# P04_POWER.net
KiCad netlist of a schematic drawn in Altium Designer
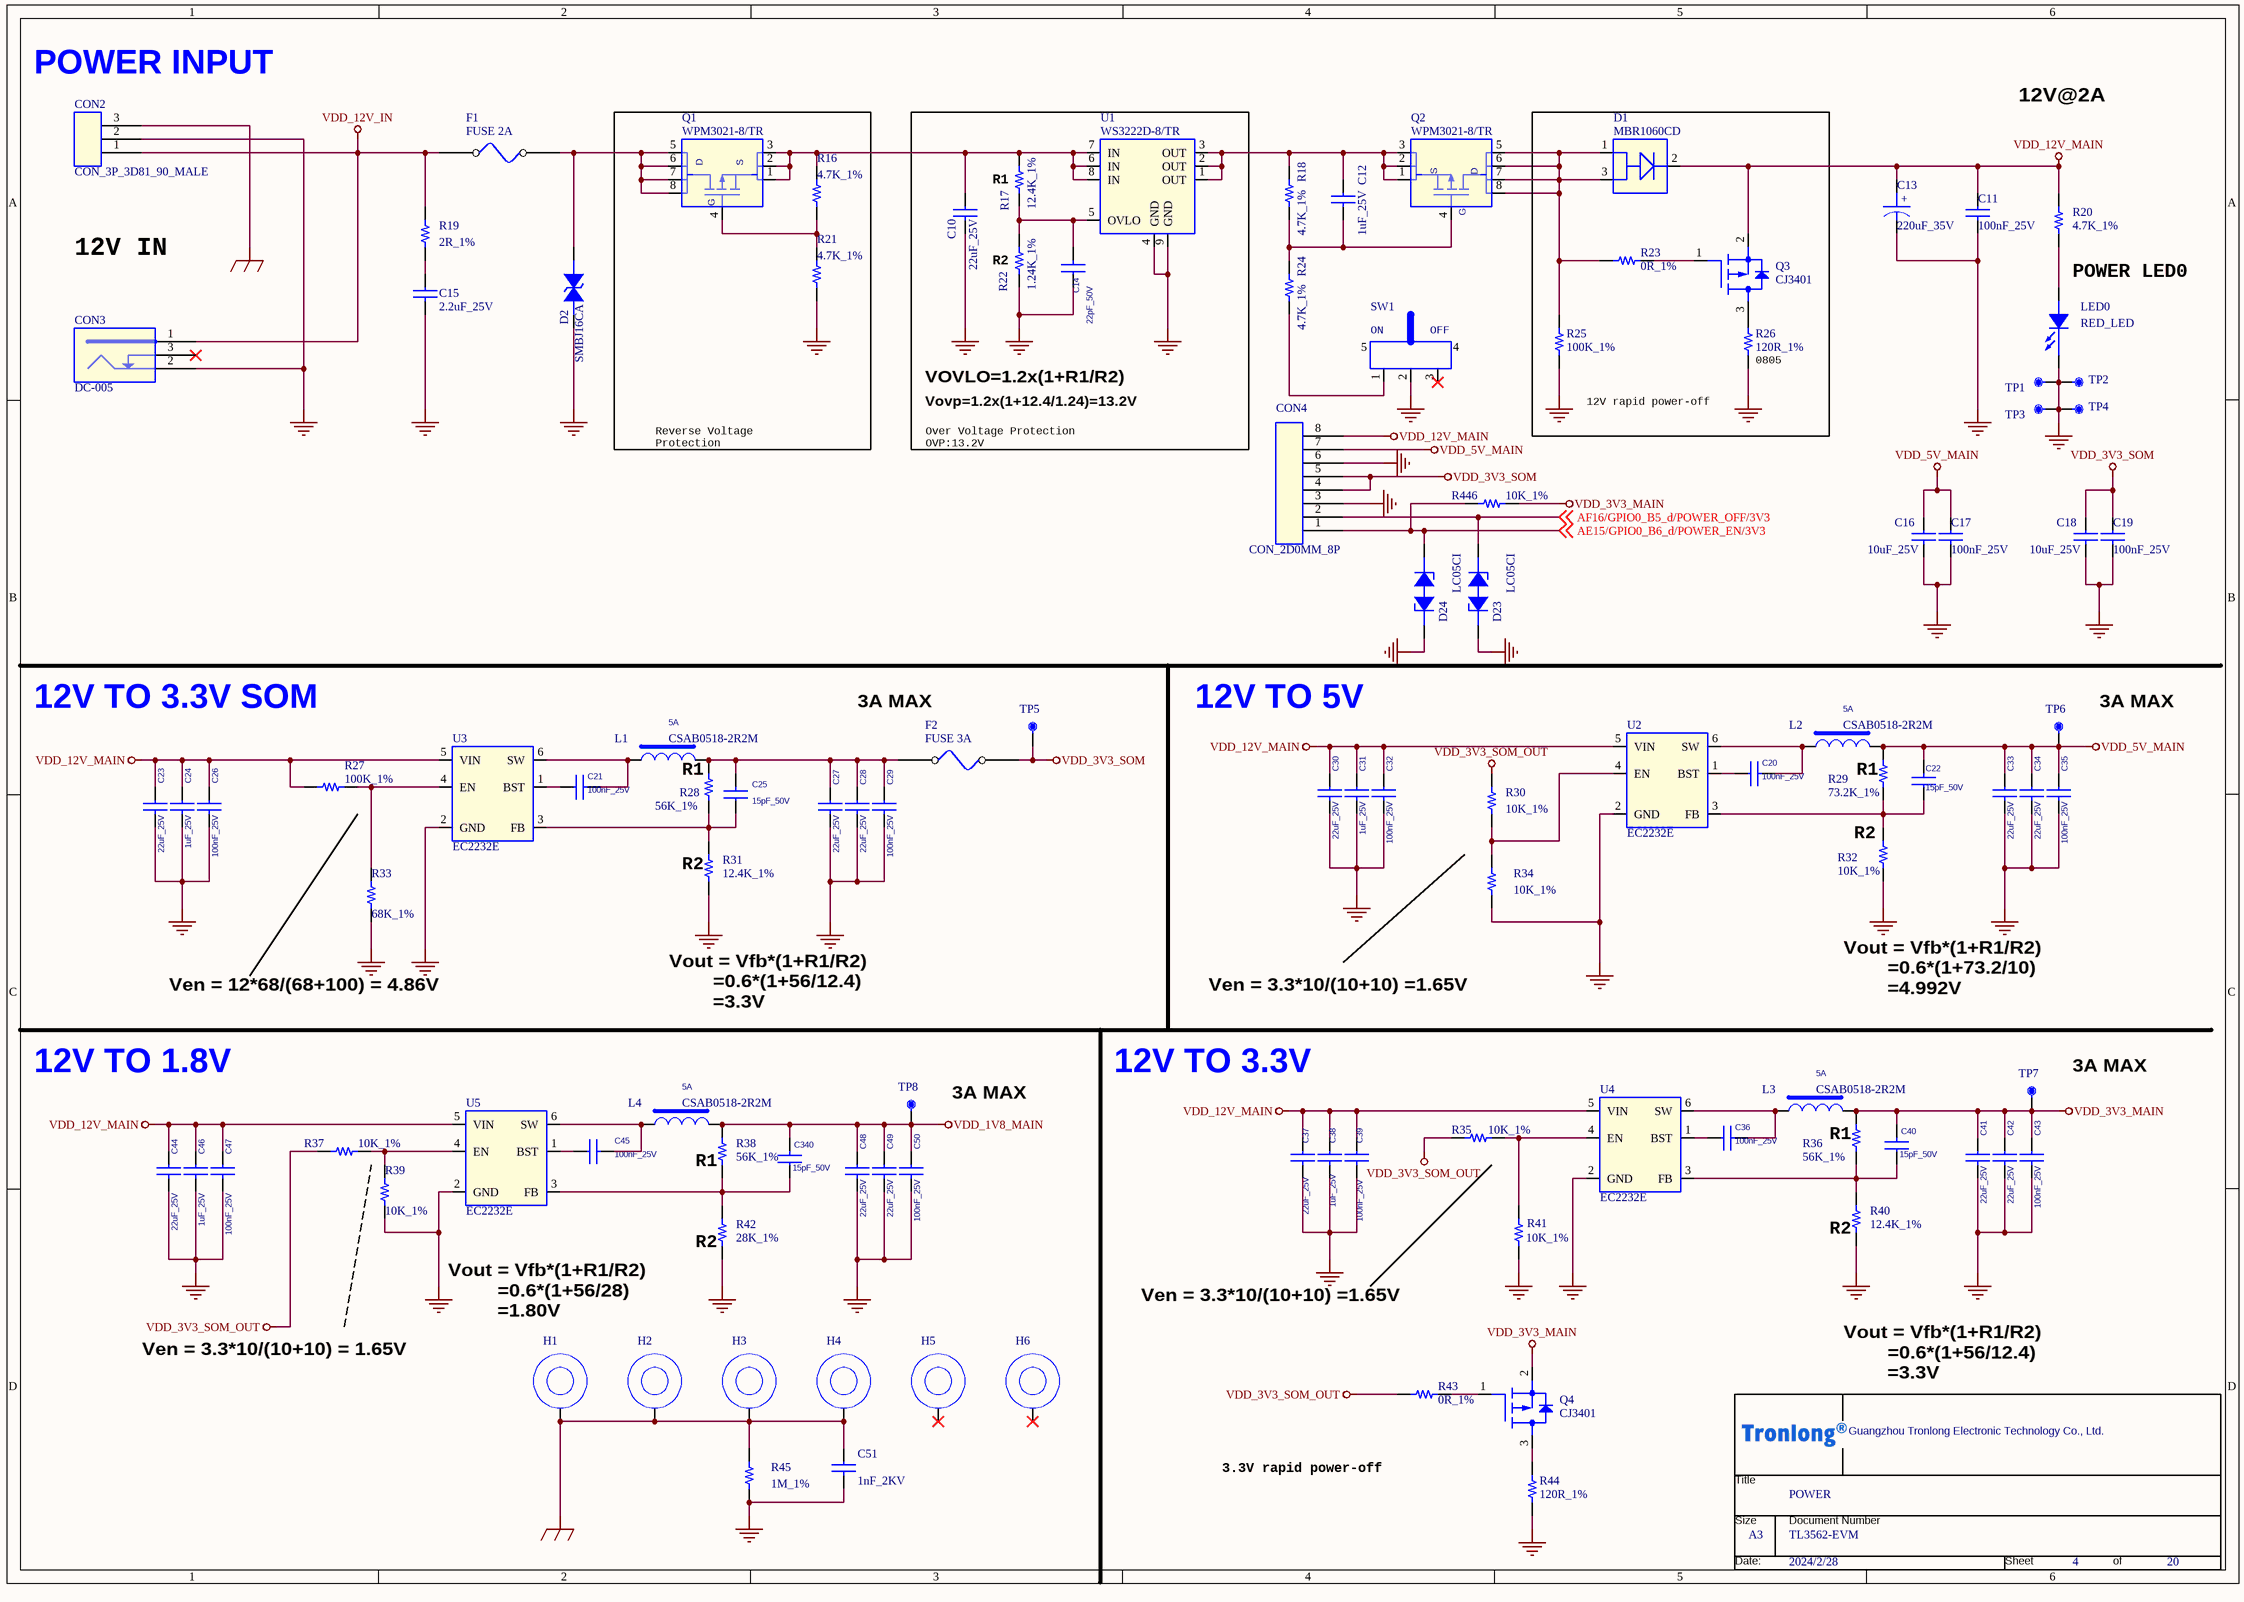
[diagram p0: P04_POWER.SchDoc]

(export (version "E")
  (design (tool "Eeschema 10.0.6"))
  (components
    (comp (ref "C10")
      (value "22uF_25V")
      (footprint "C0805")
      (description "贴片陶瓷电容,22uF,20%,25V,X5R")
      (libsource (lib "*") (part "CAP NP_Dup3"))
    )
    (comp (ref "C11")
      (value "100nF_25V")
      (footprint "C0402")
      (description "贴片陶瓷电容,100nF,10%,25V,X5R")
      (libsource (lib "*") (part "CAP NP_Dup3"))
    )
    (comp (ref "C12")
      (value "1uF_25V")
      (footprint "C0603")
      (description "贴片陶瓷电容,1uF,10%,25V,X5R")
      (libsource (lib "*") (part "CAP NP_Dup3"))
    )
    (comp (ref "C13")
      (value "220uF_35V")
      (footprint "cap_alu_smd_8x10d5")
      (description "贴片式铝电解电容,220uF,20%,35V")
      (fields
        (field (name "MANUFACTURER PARTNUMBER") "RVT1V221M0810VG")
        (field (name "MANUFACTURER") "东莞市合粤电子有限公司（Heyue）")
      )
      (libsource (lib "*") (part "CAP POL_Dup1"))
    )
    (comp (ref "C14")
      (value "22pF_50V")
      (footprint "C0603")
      (description "贴片陶瓷电容,22pF,5%,50V,C0G")
      (libsource (lib "*") (part "CAP NP_Dup3"))
    )
    (comp (ref "C15")
      (value "2.2uF_25V")
      (footprint "C1206")
      (description "贴片陶瓷电容,2.2uF,20%,25V,Y5V")
      (libsource (lib "*") (part "CAP NP_Dup3"))
    )
    (comp (ref "C16")
      (value "10uF_25V")
      (footprint "C0603")
      (description "贴片陶瓷电容,10uF,10%,10V,X5R")
      (libsource (lib "*") (part "CAP NP_Dup3"))
    )
    (comp (ref "C17")
      (value "100nF_25V")
      (footprint "C0402")
      (description "贴片陶瓷电容,100nF,10%,25V,X5R")
      (libsource (lib "*") (part "CAP NP_Dup3"))
    )
    (comp (ref "C18")
      (value "10uF_25V")
      (footprint "C0603")
      (description "贴片陶瓷电容,10uF,10%,10V,X5R")
      (libsource (lib "*") (part "CAP NP_Dup3"))
    )
    (comp (ref "C19")
      (value "100nF_25V")
      (footprint "C0402")
      (description "贴片陶瓷电容,100nF,10%,25V,X5R")
      (libsource (lib "*") (part "CAP NP_Dup3"))
    )
    (comp (ref "C20")
      (value "100nF_25V")
      (footprint "C0402")
      (description "贴片陶瓷电容,100nF,10%,25V,X5R")
      (libsource (lib "*") (part "CAP NP_Dup3"))
    )
    (comp (ref "C21")
      (value "100nF_25V")
      (footprint "C0402")
      (description "贴片陶瓷电容,100nF,10%,25V,X5R")
      (libsource (lib "*") (part "CAP NP_Dup3"))
    )
    (comp (ref "C22")
      (value "15pF_50V")
      (footprint "C0402")
      (description "贴片陶瓷电容,15pF,5%,50V,COG")
      (libsource (lib "*") (part "CAP NP_Dup3"))
    )
    (comp (ref "C23")
      (value "22uF_25V")
      (footprint "C0805")
      (description "贴片陶瓷电容,22uF,20%,25V,X5R")
      (libsource (lib "*") (part "CAP NP_Dup3"))
    )
    (comp (ref "C24")
      (value "1uF_25V")
      (footprint "C0603")
      (description "贴片陶瓷电容,1uF,10%,25V,X5R")
      (libsource (lib "*") (part "CAP NP_Dup3"))
    )
    (comp (ref "C25")
      (value "15pF_50V")
      (footprint "C0402")
      (description "贴片陶瓷电容,15pF,5%,50V,COG")
      (libsource (lib "*") (part "CAP NP_Dup3"))
    )
    (comp (ref "C26")
      (value "100nF_25V")
      (footprint "C0402")
      (description "贴片陶瓷电容,100nF,10%,25V,X5R")
      (libsource (lib "*") (part "CAP NP_Dup3"))
    )
    (comp (ref "C27")
      (value "22uF_25V")
      (footprint "C0805")
      (description "贴片陶瓷电容,22uF,20%,25V,X5R")
      (libsource (lib "*") (part "CAP NP_Dup3"))
    )
    (comp (ref "C28")
      (value "22uF_25V")
      (footprint "C0805")
      (description "贴片陶瓷电容,22uF,20%,25V,X5R")
      (libsource (lib "*") (part "CAP NP_Dup3"))
    )
    (comp (ref "C29")
      (value "100nF_25V")
      (footprint "C0402")
      (description "贴片陶瓷电容,100nF,10%,25V,X5R")
      (libsource (lib "*") (part "CAP NP_Dup3"))
    )
    (comp (ref "C30")
      (value "22uF_25V")
      (footprint "C0805")
      (description "贴片陶瓷电容,22uF,20%,25V,X5R")
      (libsource (lib "*") (part "CAP NP_Dup3"))
    )
    (comp (ref "C31")
      (value "1uF_25V")
      (footprint "C0603")
      (description "贴片陶瓷电容,1uF,10%,25V,X5R")
      (libsource (lib "*") (part "CAP NP_Dup3"))
    )
    (comp (ref "C32")
      (value "100nF_25V")
      (footprint "C0402")
      (description "贴片陶瓷电容,100nF,10%,25V,X5R")
      (libsource (lib "*") (part "CAP NP_Dup3"))
    )
    (comp (ref "C33")
      (value "22uF_25V")
      (footprint "C0805")
      (description "贴片陶瓷电容,22uF,20%,25V,X5R")
      (libsource (lib "*") (part "CAP NP_Dup3"))
    )
    (comp (ref "C34")
      (value "22uF_25V")
      (footprint "C0805")
      (description "贴片陶瓷电容,22uF,20%,25V,X5R")
      (libsource (lib "*") (part "CAP NP_Dup3"))
    )
    (comp (ref "C35")
      (value "100nF_25V")
      (footprint "C0402")
      (description "贴片陶瓷电容,100nF,10%,25V,X5R")
      (libsource (lib "*") (part "CAP NP_Dup3"))
    )
    (comp (ref "C36")
      (value "100nF_25V")
      (footprint "C0402")
      (description "贴片陶瓷电容,100nF,10%,25V,X5R")
      (libsource (lib "*") (part "CAP NP_Dup3"))
    )
    (comp (ref "C37")
      (value "22uF_25V")
      (footprint "C0805")
      (description "贴片陶瓷电容,22uF,20%,25V,X5R")
      (libsource (lib "*") (part "CAP NP_Dup3"))
    )
    (comp (ref "C38")
      (value "1uF_25V")
      (footprint "C0603")
      (description "贴片陶瓷电容,1uF,10%,25V,X5R")
      (libsource (lib "*") (part "CAP NP_Dup3"))
    )
    (comp (ref "C39")
      (value "100nF_25V")
      (footprint "C0402")
      (description "贴片陶瓷电容,100nF,10%,25V,X5R")
      (libsource (lib "*") (part "CAP NP_Dup3"))
    )
    (comp (ref "C40")
      (value "15pF_50V")
      (footprint "C0402")
      (description "贴片陶瓷电容,15pF,5%,50V,COG")
      (libsource (lib "*") (part "CAP NP_Dup3"))
    )
    (comp (ref "C41")
      (value "22uF_25V")
      (footprint "C0805")
      (description "贴片陶瓷电容,22uF,20%,25V,X5R")
      (libsource (lib "*") (part "CAP NP_Dup3"))
    )
    (comp (ref "C42")
      (value "22uF_25V")
      (footprint "C0805")
      (description "贴片陶瓷电容,22uF,20%,25V,X5R")
      (libsource (lib "*") (part "CAP NP_Dup3"))
    )
    (comp (ref "C43")
      (value "100nF_25V")
      (footprint "C0402")
      (description "贴片陶瓷电容,100nF,10%,25V,X5R")
      (libsource (lib "*") (part "CAP NP_Dup3"))
    )
    (comp (ref "C44")
      (value "22uF_25V")
      (footprint "C0805")
      (description "贴片陶瓷电容,22uF,20%,25V,X5R")
      (libsource (lib "*") (part "CAP NP_Dup3"))
    )
    (comp (ref "C45")
      (value "100nF_25V")
      (footprint "C0402")
      (description "贴片陶瓷电容,100nF,10%,25V,X5R")
      (libsource (lib "*") (part "CAP NP_Dup3"))
    )
    (comp (ref "C46")
      (value "1uF_25V")
      (footprint "C0603")
      (description "贴片陶瓷电容,1uF,10%,25V,X5R")
      (libsource (lib "*") (part "CAP NP_Dup3"))
    )
    (comp (ref "C47")
      (value "100nF_25V")
      (footprint "C0402")
      (description "贴片陶瓷电容,100nF,10%,25V,X5R")
      (libsource (lib "*") (part "CAP NP_Dup3"))
    )
    (comp (ref "C48")
      (value "22uF_25V")
      (footprint "C0805")
      (description "贴片陶瓷电容,22uF,20%,25V,X5R")
      (libsource (lib "*") (part "CAP NP_Dup3"))
    )
    (comp (ref "C49")
      (value "22uF_25V")
      (footprint "C0805")
      (description "贴片陶瓷电容,22uF,20%,25V,X5R")
      (libsource (lib "*") (part "CAP NP_Dup3"))
    )
    (comp (ref "C50")
      (value "100nF_25V")
      (footprint "C0402")
      (description "贴片陶瓷电容,100nF,10%,25V,X5R")
      (libsource (lib "*") (part "CAP NP_Dup3"))
    )
    (comp (ref "C51")
      (value "1nF_2KV")
      (footprint "C1210")
      (description "贴片陶瓷电容,1nF,10%,2KV,X7R")
      (libsource (lib "*") (part "CAP NP_Dup3"))
    )
    (comp (ref "C340")
      (value "15pF_50V")
      (footprint "C0402")
      (description "贴片陶瓷电容,15pF,5%,50V,COG")
      (libsource (lib "*") (part "CAP NP_Dup3"))
    )
    (comp (ref "CON2")
      (value "CON_3P_3D81_90_MALE")
      (footprint "CON_3P_3D81_90_MALE_NEW")
      (description "端子座,3PIN,间距3.81MM,90度,绿色,插件")
      (fields
        (field (name "MANUFACTURER PARTNUMBER") "KF2EDGR-3.81-03P-14")
        (field (name "MANUFACTURER") "慈溪市科发电子有限公司（KEFA）")
      )
      (libsource (lib "*") (part "CON3_Dup1"))
    )
    (comp (ref "CON3")
      (value "DC-005")
      (footprint "con_dc005_new")
      (description "DC-005,3PIN,90度,母座,2.0MM内径,插件")
      (fields
        (field (name "MANUFACTURER") "广东纳特康电子股份有限公司(natconn)")
        (field (name "MANUFACTURER PARTNUMBER") "305-OT03SZD001")
      )
      (libsource (lib "*") (part "DC-005"))
    )
    (comp (ref "CON4")
      (value "CON_2D0MM_8P")
      (footprint "DIP_CON_2D0MM_8P")
      (description "端子座,1x8PIN,间距2.00MM,180度,插件")
      (fields
        (field (name "MANUFACTURER") "深圳市长江连接器有限公司（CJT）")
        (field (name "MANUFACTURER PARTNUMBER") "A2001WV-8P-3")
      )
      (libsource (lib "*") (part "CON8"))
    )
    (comp (ref "D1")
      (value "MBR1060CD")
      (footprint "TO-252")
      (description "肖特基二极管,VR=60V,IF=10A,VF=0.75V@5A,两路")
      (fields (field (name "MANUFACTURER") "辽宁芯诺电子科技有限公司（XINNUO）"))
      (libsource (lib "*") (part "MBRB1045_0"))
    )
    (comp (ref "D2")
      (value "SMBJ16CA")
      (footprint "SMB")
      (description "TVS二极管,VRWM=16V,VBR=17.8V,一组,双向")
      (fields (field (name "MANUFACTURER") "江苏长晶科技有限公司（JSCJ）"))
      (libsource (lib "*") (part "DIODE-TRIG"))
    )
    (comp (ref "D23")
      (value "LC05CI")
      (footprint "SOD323_BI")
      (description "TVS二极管,VRWM=5V,VBR=6V,一组,双向,30KV,30KV")
      (fields
        (field (name "MANUFACTURER PART NUMBER") "PESD3V3L1BA")
        (field (name "MANUFACTURER") "上海雷卯电子科技有限公司（Leiditech）")
      )
      (libsource (lib "*") (part "DIODE BREAKDOWN_2"))
    )
    (comp (ref "D24")
      (value "LC05CI")
      (footprint "SOD323_BI")
      (description "TVS二极管,VRWM=5V,VBR=6V,一组,双向,30KV,30KV")
      (fields
        (field (name "MANUFACTURER PART NUMBER") "PESD3V3L1BA")
        (field (name "MANUFACTURER") "上海雷卯电子科技有限公司（Leiditech）")
      )
      (libsource (lib "*") (part "DIODE BREAKDOWN_2"))
    )
    (comp (ref "F1")
      (value "FUSE 2A")
      (footprint "F1206")
      (description "保险丝，Vmax=72V,Imax=50A,Ihold=2A")
      (fields
        (field (name "MANUFACTURER PARTNUMBER") "F12T2")
        (field (name "MANUFACTURER") "东莞市竞沃电子科技有限公司（TLC）")
      )
      (libsource (lib "*") (part "FUSE"))
    )
    (comp (ref "F2")
      (value "FUSE 3A")
      (footprint "F1206")
      (description "保险丝，Vmax=72V,Imax=50A,Ihold=3A")
      (fields
        (field (name "MANUFACTURER PARTNUMBER") "F12T3")
        (field (name "MANUFACTURER") "东莞市竞沃电子科技有限公司（TLC）")
      )
      (libsource (lib "*") (part "FUSE"))
    )
    (comp (ref "H1") (value "HOLE") (footprint "MHOLE_C200D125") (libsource (lib "*") (part "HOLE")))
    (comp (ref "H2") (value "HOLE") (footprint "MHOLE_C200D125") (libsource (lib "*") (part "HOLE")))
    (comp (ref "H3") (value "HOLE") (footprint "MHOLE_C200D125") (libsource (lib "*") (part "HOLE")))
    (comp (ref "H4") (value "HOLE") (footprint "MHOLE_C200D125") (libsource (lib "*") (part "HOLE")))
    (comp (ref "H5") (value "HOLE") (footprint "MHOLE_C200D125") (libsource (lib "*") (part "HOLE")))
    (comp (ref "H6") (value "HOLE") (footprint "MHOLE_C200D125") (libsource (lib "*") (part "HOLE")))
    (comp (ref "L1")
      (value "CSAB0518-2R2M")
      (footprint "SMD_CSAB0518")
      (description "贴片功率电感,2.2uH,0.035Ω,Isat=6.5A,Irms=5A")
      (fields (field (name "MANUFACTURER") "深圳市科达嘉电子有限公司（CODACA）") (field (name "CURRENT") "5A"))
      (libsource (lib "TL3562-EVM-A1-0-000-D-20231116") (part "INDUCTOR"))
    )
    (comp (ref "L2")
      (value "CSAB0518-2R2M")
      (footprint "SMD_CSAB0518")
      (description "贴片功率电感,2.2uH,0.035Ω,Isat=6.5A,Irms=5A")
      (fields (field (name "MANUFACTURER") "深圳市科达嘉电子有限公司（CODACA）") (field (name "CURRENT") "5A"))
      (libsource (lib "TL3562-EVM-A1-0-000-D-20231116") (part "INDUCTOR"))
    )
    (comp (ref "L3")
      (value "CSAB0518-2R2M")
      (footprint "SMD_CSAB0518")
      (description "贴片功率电感,2.2uH,0.035Ω,Isat=6.5A,Irms=5A")
      (fields (field (name "MANUFACTURER") "深圳市科达嘉电子有限公司（CODACA）") (field (name "CURRENT") "5A"))
      (libsource (lib "TL3562-EVM-A1-0-000-D-20231116") (part "INDUCTOR"))
    )
    (comp (ref "L4")
      (value "CSAB0518-2R2M")
      (footprint "SMD_CSAB0518")
      (description "贴片功率电感,2.2uH,0.035Ω,Isat=6.5A,Irms=5A")
      (fields (field (name "MANUFACTURER") "深圳市科达嘉电子有限公司（CODACA）") (field (name "CURRENT") "5A"))
      (libsource (lib "TL3562-EVM-A1-0-000-D-20231116") (part "INDUCTOR"))
    )
    (comp (ref "LED0")
      (value "RED_LED")
      (footprint "CON_2P_3MM")
      (description "直插式发光二极管,红色,带灯座")
      (fields
        (field (name "MANUFACTURER PARTNUMBER") "JH-03B2RD1E-DL")
        (field (name "MANUFACTURER") "深圳市巨弘光电有限公司（JUHLIGHT）")
      )
      (libsource (lib "*") (part "LED"))
    )
    (comp (ref "Q1")
      (value "WPM3021-8/TR")
      (footprint "PSOPSOP-8L")
      (description "MOSFET,P沟道,VDSS=-30V,VGSS=±25V,ID=-13A,PD=3.8W,VGS(th)=-3V")
      (fields (field (name "MANUFACTURER") "上海韦尔半导体股份有限公司（WILLSEMI）"))
      (libsource (lib "*") (part "WPM3021"))
    )
    (comp (ref "Q2")
      (value "WPM3021-8/TR")
      (footprint "PSOPSOP-8L")
      (description "MOSFET,P沟道,VDSS=-30V,VGSS=±25V,ID=-13A,PD=3.8W,VGS(th)=-3V")
      (fields (field (name "MANUFACTURER") "上海韦尔半导体股份有限公司（WILLSEMI）"))
      (libsource (lib "") (part "WPM3021_1"))
    )
    (comp (ref "Q3")
      (value "CJ3401")
      (footprint "SOT23-3")
      (description "MOSFET,P沟道,VDSS=-30V,VGSS=±12V,ID=-4.2A,PD=0.35W,VGS(th)=-1.3V")
      (fields (field (name "MANUFACTURER") "江苏长晶科技有限公司（JSCJ）"))
      (libsource (lib "*") (part "MOSFET P SOT_Dup1"))
    )
    (comp (ref "Q4")
      (value "CJ3401")
      (footprint "SOT23-3")
      (description "MOSFET,P沟道,VDSS=-30V,VGSS=±12V,ID=-4.2A,PD=0.35W,VGS(th)=-1.3V")
      (fields (field (name "MANUFACTURER") "江苏长晶科技有限公司（JSCJ）"))
      (libsource (lib "*") (part "MOSFET P SOT_Dup1"))
    )
    (comp (ref "R16")
      (value "4.7K_1%")
      (footprint "R0402")
      (description "贴片电阻,4.7K,±1%,1/16W")
      (libsource (lib "*") (part "Resistor_Dup3"))
    )
    (comp (ref "R17")
      (value "12.4K_1%")
      (footprint "R0402")
      (description "贴片电阻,12.4K,±1%,1/16W")
      (libsource (lib "*") (part "Resistor_Dup3"))
    )
    (comp (ref "R18")
      (value "4.7K_1%")
      (footprint "R0402")
      (description "贴片电阻,4.7K,±1%,1/16W")
      (libsource (lib "*") (part "Resistor_Dup3"))
    )
    (comp (ref "R19")
      (value "2R_1%")
      (footprint "R1210")
      (description "贴片电阻,2R,±1%,1/3W")
      (libsource (lib "*") (part "Resistor_Dup3"))
    )
    (comp (ref "R20")
      (value "4.7K_1%")
      (footprint "R0402")
      (description "贴片电阻,4.7K,±1%,1/16W")
      (libsource (lib "*") (part "Resistor_Dup3"))
    )
    (comp (ref "R21")
      (value "4.7K_1%")
      (footprint "R0402")
      (description "贴片电阻,4.7K,±1%,1/16W")
      (libsource (lib "*") (part "Resistor_Dup3"))
    )
    (comp (ref "R22")
      (value "1.24K_1%")
      (footprint "R0603")
      (description "贴片电阻,12.4K,±1%,1/10W")
      (libsource (lib "*") (part "Resistor_Dup3"))
    )
    (comp (ref "R23")
      (value "0R_1%")
      (footprint "R0402")
      (description "0R,±1%,R0402,≥1/16W")
      (libsource (lib "*") (part "Resistor_Dup3"))
    )
    (comp (ref "R24")
      (value "4.7K_1%")
      (footprint "R0402")
      (description "贴片电阻,4.7K,±1%,1/16W")
      (libsource (lib "*") (part "Resistor_Dup3"))
    )
    (comp (ref "R25")
      (value "100K_1%")
      (footprint "R0402")
      (description "贴片电阻,100K,±1%,1/16W")
      (libsource (lib "*") (part "Resistor_Dup3"))
    )
    (comp (ref "R26")
      (value "120R_1%")
      (footprint "R0805")
      (description "贴片电阻,120R,±1%,1/8W")
      (libsource (lib "*") (part "Resistor_Dup3"))
    )
    (comp (ref "R27")
      (value "100K_1%")
      (footprint "R0402")
      (description "贴片电阻,100K,±1%,1/16W")
      (libsource (lib "*") (part "Resistor_Dup3"))
    )
    (comp (ref "R28")
      (value "56K_1%")
      (footprint "R0402")
      (description "贴片电阻,56K,±1%,1/16W")
      (libsource (lib "*") (part "Resistor_Dup3"))
    )
    (comp (ref "R29")
      (value "73.2K_1%")
      (footprint "R0402")
      (description "贴片电阻,73.2K,±1%,1/16W")
      (libsource (lib "*") (part "Resistor_Dup3"))
    )
    (comp (ref "R30")
      (value "10K_1%")
      (footprint "R0402")
      (description "贴片电阻,10K,±1%,1/16W")
      (libsource (lib "*") (part "Resistor_Dup3"))
    )
    (comp (ref "R31")
      (value "12.4K_1%")
      (footprint "R0402")
      (description "贴片电阻,12.4K,±1%,1/16W")
      (libsource (lib "*") (part "Resistor_Dup3"))
    )
    (comp (ref "R32")
      (value "10K_1%")
      (footprint "R0402")
      (description "贴片电阻,10K,±1%,1/16W")
      (libsource (lib "*") (part "Resistor_Dup3"))
    )
    (comp (ref "R33")
      (value "68K_1%")
      (footprint "R0402")
      (description "贴片电阻,68K,±1%,1/16W")
      (libsource (lib "*") (part "Resistor_Dup3"))
    )
    (comp (ref "R34")
      (value "10K_1%")
      (footprint "R0402")
      (description "贴片电阻,10K,±1%,1/16W")
      (libsource (lib "*") (part "Resistor_Dup3"))
    )
    (comp (ref "R35")
      (value "10K_1%")
      (footprint "R0402")
      (description "贴片电阻,10K,±1%,1/16W")
      (libsource (lib "*") (part "Resistor_Dup3"))
    )
    (comp (ref "R36")
      (value "56K_1%")
      (footprint "R0402")
      (description "贴片电阻,56K,±1%,1/16W")
      (libsource (lib "*") (part "Resistor_Dup3"))
    )
    (comp (ref "R37")
      (value "10K_1%")
      (footprint "R0402")
      (description "贴片电阻,10K,±1%,1/16W")
      (libsource (lib "*") (part "Resistor_Dup3"))
    )
    (comp (ref "R38")
      (value "56K_1%")
      (footprint "R0402")
      (description "贴片电阻,56K,±1%,1/16W")
      (libsource (lib "*") (part "Resistor_Dup3"))
    )
    (comp (ref "R39")
      (value "10K_1%")
      (footprint "R0402")
      (description "贴片电阻,10K,±1%,1/16W")
      (libsource (lib "*") (part "Resistor_Dup3"))
    )
    (comp (ref "R40")
      (value "12.4K_1%")
      (footprint "R0402")
      (description "贴片电阻,12.4K,±1%,1/16W")
      (libsource (lib "*") (part "Resistor_Dup3"))
    )
    (comp (ref "R41")
      (value "10K_1%")
      (footprint "R0402")
      (description "贴片电阻,10K,±1%,1/16W")
      (libsource (lib "*") (part "Resistor_Dup3"))
    )
    (comp (ref "R42")
      (value "28K_1%")
      (footprint "R0402")
      (description "28K,±1%,R0402,≥1/16W")
      (libsource (lib "*") (part "Resistor_Dup3"))
    )
    (comp (ref "R43")
      (value "0R_1%")
      (footprint "R0402")
      (description "0R,±1%,R0402,≥1/16W")
      (libsource (lib "*") (part "Resistor_Dup3"))
    )
    (comp (ref "R44")
      (value "120R_1%")
      (footprint "R0805")
      (description "贴片电阻,120R,±1%,1/8W")
      (libsource (lib "*") (part "Resistor_Dup3"))
    )
    (comp (ref "R45")
      (value "1M_1%")
      (footprint "R0603")
      (description "贴片电阻,1M,±1%,1/10W")
      (libsource (lib "*") (part "Resistor_Dup3"))
    )
    (comp (ref "R446")
      (value "10K_1%")
      (footprint "R0402")
      (description "贴片电阻,10K,±1%,1/16W")
      (libsource (lib "*") (part "Resistor_Dup3"))
    )
    (comp (ref "SW1")
      (value "SS-12D11L5")
      (footprint "sw-126_76")
      (description "拨动开关，2档3脚侧拨开关,黑色,90度,短柄")
      (fields (field (name "MANUFACTURER") "广东星坤科技股份有限公司（XKB）"))
      (libsource (lib "*") (part "switch_7"))
    )
    (comp (ref "TP1")
      (value "Black Test Point")
      (footprint "TP_DIP")
      (description "黑色直插测试柱")
      (fields
        (field (name "MANUFACTURER") "深圳市保定五金塑胶有限公司")
        (field (name "MANUFACTURER PARTNUMBER") "TP-5011")
      )
      (libsource (lib "*") (part "TP-S40"))
    )
    (comp (ref "TP2")
      (value "Black Test Point")
      (footprint "TP_DIP")
      (description "黑色直插测试柱")
      (fields
        (field (name "MANUFACTURER PARTNUMBER") "TP-5011")
        (field (name "MANUFACTURER") "深圳市保定五金塑胶有限公司")
      )
      (libsource (lib "*") (part "TP-S40"))
    )
    (comp (ref "TP3")
      (value "Black Test Point")
      (footprint "TP_DIP")
      (description "黑色直插测试柱")
      (fields
        (field (name "MANUFACTURER") "深圳市保定五金塑胶有限公司")
        (field (name "MANUFACTURER PARTNUMBER") "TP-5011")
      )
      (libsource (lib "*") (part "TP-S40"))
    )
    (comp (ref "TP4")
      (value "Black Test Point")
      (footprint "TP_DIP")
      (description "黑色直插测试柱")
      (fields
        (field (name "MANUFACTURER") "深圳市保定五金塑胶有限公司")
        (field (name "MANUFACTURER PARTNUMBER") "TP-5011")
      )
      (libsource (lib "*") (part "TP-S40"))
    )
    (comp (ref "TP5") (value "SMT TP") (footprint "TP30") (libsource (lib "*") (part "TP-S40")))
    (comp (ref "TP6") (value "SMT TP") (footprint "TP30") (libsource (lib "*") (part "TP-S40")))
    (comp (ref "TP7") (value "SMT TP") (footprint "TP30") (libsource (lib "*") (part "TP-S40")))
    (comp (ref "TP8") (value "SMT TP") (footprint "TP30") (libsource (lib "*") (part "TP-S40")))
    (comp (ref "U1")
      (value "WS3222D-8/TR")
      (footprint "DFN2X2-8L")
      (description "MOSFET,P沟道,VDSS=-30V,VGSS=±25V,ID=-13A,PD=3.8W,VGS(th)=-3V")
      (fields (field (name "MANUFACTURER") "上海韦尔半导体股份有限公司（WILLSEMI）"))
      (libsource (lib "*") (part "WS3222D-8/TR"))
    )
    (comp (ref "U2")
      (value "EC2232E")
      (footprint "SOT-23-6L")
      (description "DC/DC,Buck,Vin:4.5V~17V,Vout:0.6V~6V,3A,1路")
      (fields (field (name "MANUFACTURER") "上海芯强微电子股份有限公司（Ecranic）"))
      (libsource (lib "*") (part "WD1304E30"))
    )
    (comp (ref "U3")
      (value "EC2232E")
      (footprint "SOT-23-6L")
      (description "DC/DC,Buck,Vin:4.5V~17V,Vout:0.6V~6V,3A,1路")
      (fields (field (name "MANUFACTURER") "上海芯强微电子股份有限公司（Ecranic）"))
      (libsource (lib "*") (part "WD1304E30"))
    )
    (comp (ref "U4")
      (value "EC2232E")
      (footprint "SOT-23-6L")
      (description "DC/DC,Buck,Vin:4.5V~17V,Vout:0.6V~6V,3A,1路")
      (fields (field (name "MANUFACTURER") "上海芯强微电子股份有限公司（Ecranic）"))
      (libsource (lib "*") (part "WD1304E30"))
    )
    (comp (ref "U5")
      (value "EC2232E")
      (footprint "SOT-23-6L")
      (description "DC/DC,Buck,Vin:4.5V~17V,Vout:0.6V~6V,3A,1路")
      (fields (field (name "MANUFACTURER") "上海芯强微电子股份有限公司（Ecranic）"))
      (libsource (lib "*") (part "WD1304E30_0"))
    )
  )
  (nets
    (net (code "1") (name "AE15{slash}GPIO0_B6_d{slash}POWER_EN{slash}3V3") (class "Default")
      (node (ref "CON4") (pin "1") (pinfunction "1_1") (pintype "passive"))
      (node (ref "D24") (pin "1") (pinfunction "ANODE1_1") (pintype "passive"))
      (node (ref "R446") (pin "2") (pinfunction "2_2") (pintype "passive"))
    )
    (net (code "2") (name "AF16{slash}GPIO0_B5_d{slash}POWER_OFF{slash}3V3") (class "Default")
      (node (ref "CON4") (pin "2") (pinfunction "2_2") (pintype "passive"))
      (node (ref "D23") (pin "1") (pinfunction "ANODE1_1") (pintype "passive"))
    )
    (net (code "3") (name "EGND") (class "Default")
      (node (ref "C51") (pin "1") (pinfunction "1_1") (pintype "passive"))
      (node (ref "CON2") (pin "3") (pinfunction "3_3") (pintype "passive"))
      (node (ref "H1") (pin "1") (pinfunction "1_1") (pintype "passive"))
      (node (ref "H2") (pin "1") (pinfunction "1_1") (pintype "passive"))
      (node (ref "H3") (pin "1") (pinfunction "1_1") (pintype "passive"))
      (node (ref "H4") (pin "1") (pinfunction "1_1") (pintype "passive"))
      (node (ref "R45") (pin "1") (pinfunction "1_1") (pintype "passive"))
    )
    (net (code "4") (name "GND") (class "Default")
      (node (ref "C10") (pin "2") (pinfunction "2_2") (pintype "passive"))
      (node (ref "C11") (pin "2") (pinfunction "2_2") (pintype "passive"))
      (node (ref "C13") (pin "2") (pinfunction "2_2") (pintype "passive"))
      (node (ref "C14") (pin "1") (pinfunction "1_1") (pintype "passive"))
      (node (ref "C15") (pin "2") (pinfunction "2_2") (pintype "passive"))
      (node (ref "C16") (pin "2") (pinfunction "2_2") (pintype "passive"))
      (node (ref "C17") (pin "2") (pinfunction "2_2") (pintype "passive"))
      (node (ref "C18") (pin "2") (pinfunction "2_2") (pintype "passive"))
      (node (ref "C19") (pin "2") (pinfunction "2_2") (pintype "passive"))
      (node (ref "C23") (pin "2") (pinfunction "2_2") (pintype "passive"))
      (node (ref "C24") (pin "2") (pinfunction "2_2") (pintype "passive"))
      (node (ref "C26") (pin "2") (pinfunction "2_2") (pintype "passive"))
      (node (ref "C27") (pin "2") (pinfunction "2_2") (pintype "passive"))
      (node (ref "C28") (pin "2") (pinfunction "2_2") (pintype "passive"))
      (node (ref "C29") (pin "2") (pinfunction "2_2") (pintype "passive"))
      (node (ref "C30") (pin "2") (pinfunction "2_2") (pintype "passive"))
      (node (ref "C31") (pin "2") (pinfunction "2_2") (pintype "passive"))
      (node (ref "C32") (pin "2") (pinfunction "2_2") (pintype "passive"))
      (node (ref "C33") (pin "2") (pinfunction "2_2") (pintype "passive"))
      (node (ref "C34") (pin "2") (pinfunction "2_2") (pintype "passive"))
      (node (ref "C35") (pin "2") (pinfunction "2_2") (pintype "passive"))
      (node (ref "C37") (pin "2") (pinfunction "2_2") (pintype "passive"))
      (node (ref "C38") (pin "2") (pinfunction "2_2") (pintype "passive"))
      (node (ref "C39") (pin "2") (pinfunction "2_2") (pintype "passive"))
      (node (ref "C41") (pin "2") (pinfunction "2_2") (pintype "passive"))
      (node (ref "C42") (pin "2") (pinfunction "2_2") (pintype "passive"))
      (node (ref "C43") (pin "2") (pinfunction "2_2") (pintype "passive"))
      (node (ref "C44") (pin "2") (pinfunction "2_2") (pintype "passive"))
      (node (ref "C46") (pin "2") (pinfunction "2_2") (pintype "passive"))
      (node (ref "C47") (pin "2") (pinfunction "2_2") (pintype "passive"))
      (node (ref "C48") (pin "2") (pinfunction "2_2") (pintype "passive"))
      (node (ref "C49") (pin "2") (pinfunction "2_2") (pintype "passive"))
      (node (ref "C50") (pin "2") (pinfunction "2_2") (pintype "passive"))
      (node (ref "C51") (pin "2") (pinfunction "2_2") (pintype "passive"))
      (node (ref "CON2") (pin "2") (pinfunction "2_2") (pintype "passive"))
      (node (ref "CON3") (pin "2") (pinfunction "22_2") (pintype "passive"))
      (node (ref "CON4") (pin "3") (pinfunction "3_3") (pintype "passive"))
      (node (ref "CON4") (pin "6") (pinfunction "6_6") (pintype "passive"))
      (node (ref "D2") (pin "1") (pinfunction "1_1") (pintype "passive"))
      (node (ref "D23") (pin "2") (pinfunction "CATHODE2_2") (pintype "passive"))
      (node (ref "D24") (pin "2") (pinfunction "CATHODE2_2") (pintype "passive"))
      (node (ref "LED0") (pin "2") (pinfunction "CATHODE_2") (pintype "passive"))
      (node (ref "R21") (pin "1") (pinfunction "1_1") (pintype "passive"))
      (node (ref "R22") (pin "2") (pinfunction "2_2") (pintype "passive"))
      (node (ref "R25") (pin "1") (pinfunction "1_1") (pintype "passive"))
      (node (ref "R26") (pin "2") (pinfunction "2_2") (pintype "passive"))
      (node (ref "R31") (pin "1") (pinfunction "1_1") (pintype "passive"))
      (node (ref "R32") (pin "1") (pinfunction "1_1") (pintype "passive"))
      (node (ref "R33") (pin "1") (pinfunction "1_1") (pintype "passive"))
      (node (ref "R34") (pin "1") (pinfunction "1_1") (pintype "passive"))
      (node (ref "R39") (pin "1") (pinfunction "1_1") (pintype "passive"))
      (node (ref "R40") (pin "1") (pinfunction "1_1") (pintype "passive"))
      (node (ref "R41") (pin "1") (pinfunction "1_1") (pintype "passive"))
      (node (ref "R42") (pin "1") (pinfunction "1_1") (pintype "passive"))
      (node (ref "R44") (pin "2") (pinfunction "2_2") (pintype "passive"))
      (node (ref "R45") (pin "2") (pinfunction "2_2") (pintype "passive"))
      (node (ref "SW1") (pin "2") (pinfunction "2_2") (pintype "passive"))
      (node (ref "TP1") (pin "1") (pinfunction "1_1") (pintype "passive"))
      (node (ref "TP2") (pin "1") (pinfunction "1_1") (pintype "passive"))
      (node (ref "TP3") (pin "1") (pinfunction "1_1") (pintype "passive"))
      (node (ref "TP4") (pin "1") (pinfunction "1_1") (pintype "passive"))
      (node (ref "U1") (pin "4") (pinfunction "GND_4") (pintype "power_in"))
      (node (ref "U1") (pin "9") (pinfunction "GND_9") (pintype "power_in"))
      (node (ref "U2") (pin "2") (pinfunction "GND_2") (pintype "power_in"))
      (node (ref "U3") (pin "2") (pinfunction "GND_2") (pintype "power_in"))
      (node (ref "U4") (pin "2") (pinfunction "GND_2") (pintype "power_in"))
      (node (ref "U5") (pin "2") (pinfunction "GND_2") (pintype "power_in"))
    )
    (net (code "5") (name "Net-(C15-Pad1)") (class "Default")
      (node (ref "C15") (pin "1") (pinfunction "1_1") (pintype "passive"))
      (node (ref "R19") (pin "1") (pinfunction "1_1") (pintype "passive"))
    )
    (net (code "6") (name "Net-(C25-Pad2)") (class "Default")
      (node (ref "C25") (pin "2") (pinfunction "2_2") (pintype "passive"))
      (node (ref "C27") (pin "1") (pinfunction "1_1") (pintype "passive"))
      (node (ref "C28") (pin "1") (pinfunction "1_1") (pintype "passive"))
      (node (ref "C29") (pin "1") (pinfunction "1_1") (pintype "passive"))
      (node (ref "F2") (pin "1") (pinfunction "1_1") (pintype "passive"))
      (node (ref "L1") (pin "2") (pinfunction "2_2") (pintype "passive"))
      (node (ref "R28") (pin "2") (pinfunction "2_2") (pintype "passive"))
    )
    (net (code "7") (name "Net-(LED0-ANODE)") (class "Default")
      (node (ref "LED0") (pin "1") (pinfunction "ANODE_1") (pintype "passive"))
      (node (ref "R20") (pin "2") (pinfunction "2_2") (pintype "passive"))
    )
    (net (code "8") (name "Net-(Q1-D1)") (class "Default")
      (node (ref "D2") (pin "2") (pinfunction "2_2") (pintype "passive"))
      (node (ref "F1") (pin "2") (pinfunction "2_2") (pintype "passive"))
      (node (ref "Q1") (pin "5") (pinfunction "D1_5") (pintype "passive"))
      (node (ref "Q1") (pin "6") (pinfunction "D2_6") (pintype "passive"))
      (node (ref "Q1") (pin "7") (pinfunction "D3_7") (pintype "passive"))
      (node (ref "Q1") (pin "8") (pinfunction "D4_8") (pintype "passive"))
    )
    (net (code "9") (name "Net-(Q1-G)") (class "Default")
      (node (ref "Q1") (pin "4") (pinfunction "G_4") (pintype "passive"))
      (node (ref "R16") (pin "1") (pinfunction "1_1") (pintype "passive"))
      (node (ref "R21") (pin "2") (pinfunction "2_2") (pintype "passive"))
    )
    (net (code "10") (name "Net-(Q1-S1)") (class "Default")
      (node (ref "C10") (pin "1") (pinfunction "1_1") (pintype "passive"))
      (node (ref "Q1") (pin "1") (pinfunction "S1_1") (pintype "passive"))
      (node (ref "Q1") (pin "2") (pinfunction "S2_2") (pintype "passive"))
      (node (ref "Q1") (pin "3") (pinfunction "S3_3") (pintype "passive"))
      (node (ref "R16") (pin "2") (pinfunction "2_2") (pintype "passive"))
      (node (ref "R17") (pin "1") (pinfunction "1_1") (pintype "passive"))
      (node (ref "U1") (pin "6") (pinfunction "IN_6") (pintype "power_in"))
      (node (ref "U1") (pin "7") (pinfunction "IN_7") (pintype "power_in"))
      (node (ref "U1") (pin "8") (pinfunction "IN_8") (pintype "power_in"))
    )
    (net (code "11") (name "Net-(Q2-D1)") (class "Default")
      (node (ref "D1") (pin "1") (pinfunction "1_1") (pintype "passive"))
      (node (ref "D1") (pin "3") (pinfunction "3_3") (pintype "passive"))
      (node (ref "Q2") (pin "5") (pinfunction "D1_5") (pintype "passive"))
      (node (ref "Q2") (pin "6") (pinfunction "D2_6") (pintype "passive"))
      (node (ref "Q2") (pin "7") (pinfunction "D3_7") (pintype "passive"))
      (node (ref "Q2") (pin "8") (pinfunction "D4_8") (pintype "passive"))
      (node (ref "R23") (pin "2") (pinfunction "2_2") (pintype "passive"))
      (node (ref "R25") (pin "2") (pinfunction "2_2") (pintype "passive"))
    )
    (net (code "12") (name "Net-(Q2-G)") (class "Default")
      (node (ref "C12") (pin "2") (pinfunction "2_2") (pintype "passive"))
      (node (ref "Q2") (pin "4") (pinfunction "G_4") (pintype "passive"))
      (node (ref "R18") (pin "1") (pinfunction "1_1") (pintype "passive"))
      (node (ref "R24") (pin "2") (pinfunction "2_2") (pintype "passive"))
    )
    (net (code "13") (name "Net-(Q2-S1)") (class "Default")
      (node (ref "C12") (pin "1") (pinfunction "1_1") (pintype "passive"))
      (node (ref "Q2") (pin "1") (pinfunction "S1_1") (pintype "passive"))
      (node (ref "Q2") (pin "2") (pinfunction "S2_2") (pintype "passive"))
      (node (ref "Q2") (pin "3") (pinfunction "S3_3") (pintype "passive"))
      (node (ref "R18") (pin "2") (pinfunction "2_2") (pintype "passive"))
      (node (ref "U1") (pin "1") (pinfunction "OUT_1") (pintype "power_in"))
      (node (ref "U1") (pin "2") (pinfunction "OUT_2") (pintype "power_in"))
      (node (ref "U1") (pin "3") (pinfunction "OUT_3") (pintype "power_in"))
    )
    (net (code "14") (name "Net-(Q3-DRAIN)") (class "Default")
      (node (ref "Q3") (pin "3") (pinfunction "DRAIN_3") (pintype "passive"))
      (node (ref "R26") (pin "1") (pinfunction "1_1") (pintype "passive"))
    )
    (net (code "15") (name "Net-(Q3-GATE)") (class "Default")
      (node (ref "Q3") (pin "1") (pinfunction "GATE_1") (pintype "passive"))
      (node (ref "R23") (pin "1") (pinfunction "1_1") (pintype "passive"))
    )
    (net (code "16") (name "Net-(Q4-DRAIN)") (class "Default")
      (node (ref "Q4") (pin "3") (pinfunction "DRAIN_3") (pintype "passive"))
      (node (ref "R44") (pin "1") (pinfunction "1_1") (pintype "passive"))
    )
    (net (code "17") (name "Net-(Q4-GATE)") (class "Default")
      (node (ref "Q4") (pin "1") (pinfunction "GATE_1") (pintype "passive"))
      (node (ref "R43") (pin "1") (pinfunction "1_1") (pintype "passive"))
    )
    (net (code "18") (name "Net-(R24-Pad1)") (class "Default")
      (node (ref "R24") (pin "1") (pinfunction "1_1") (pintype "passive"))
      (node (ref "SW1") (pin "1") (pinfunction "1_1") (pintype "passive"))
    )
    (net (code "19") (name "Net-(U1-OVLO)") (class "Default")
      (node (ref "C14") (pin "2") (pinfunction "2_2") (pintype "passive"))
      (node (ref "R17") (pin "2") (pinfunction "2_2") (pintype "passive"))
      (node (ref "R22") (pin "1") (pinfunction "1_1") (pintype "passive"))
      (node (ref "U1") (pin "5") (pinfunction "OVLO_5") (pintype "passive"))
    )
    (net (code "20") (name "Net-(U2-BST)") (class "Default")
      (node (ref "C20") (pin "1") (pinfunction "1_1") (pintype "passive"))
      (node (ref "U2") (pin "1") (pinfunction "BST_1") (pintype "passive"))
    )
    (net (code "21") (name "Net-(U2-EN)") (class "Default")
      (node (ref "R30") (pin "1") (pinfunction "1_1") (pintype "passive"))
      (node (ref "R34") (pin "2") (pinfunction "2_2") (pintype "passive"))
      (node (ref "U2") (pin "4") (pinfunction "EN_4") (pintype "passive"))
    )
    (net (code "22") (name "Net-(U2-FB)") (class "Default")
      (node (ref "C22") (pin "1") (pinfunction "1_1") (pintype "passive"))
      (node (ref "R29") (pin "1") (pinfunction "1_1") (pintype "passive"))
      (node (ref "R32") (pin "2") (pinfunction "2_2") (pintype "passive"))
      (node (ref "U2") (pin "3") (pinfunction "FB_3") (pintype "passive"))
    )
    (net (code "23") (name "Net-(U2-SW)") (class "Default")
      (node (ref "C20") (pin "2") (pinfunction "2_2") (pintype "passive"))
      (node (ref "L2") (pin "1") (pinfunction "1_1") (pintype "passive"))
      (node (ref "U2") (pin "6") (pinfunction "SW_6") (pintype "passive"))
    )
    (net (code "24") (name "Net-(U3-BST)") (class "Default")
      (node (ref "C21") (pin "1") (pinfunction "1_1") (pintype "passive"))
      (node (ref "U3") (pin "1") (pinfunction "BST_1") (pintype "passive"))
    )
    (net (code "25") (name "Net-(U3-EN)") (class "Default")
      (node (ref "R27") (pin "2") (pinfunction "2_2") (pintype "passive"))
      (node (ref "R33") (pin "2") (pinfunction "2_2") (pintype "passive"))
      (node (ref "U3") (pin "4") (pinfunction "EN_4") (pintype "passive"))
    )
    (net (code "26") (name "Net-(U3-FB)") (class "Default")
      (node (ref "C25") (pin "1") (pinfunction "1_1") (pintype "passive"))
      (node (ref "R28") (pin "1") (pinfunction "1_1") (pintype "passive"))
      (node (ref "R31") (pin "2") (pinfunction "2_2") (pintype "passive"))
      (node (ref "U3") (pin "3") (pinfunction "FB_3") (pintype "passive"))
    )
    (net (code "27") (name "Net-(U3-SW)") (class "Default")
      (node (ref "C21") (pin "2") (pinfunction "2_2") (pintype "passive"))
      (node (ref "L1") (pin "1") (pinfunction "1_1") (pintype "passive"))
      (node (ref "U3") (pin "6") (pinfunction "SW_6") (pintype "passive"))
    )
    (net (code "28") (name "Net-(U4-BST)") (class "Default")
      (node (ref "C36") (pin "1") (pinfunction "1_1") (pintype "passive"))
      (node (ref "U4") (pin "1") (pinfunction "BST_1") (pintype "passive"))
    )
    (net (code "29") (name "Net-(U4-EN)") (class "Default")
      (node (ref "R35") (pin "1") (pinfunction "1_1") (pintype "passive"))
      (node (ref "R41") (pin "2") (pinfunction "2_2") (pintype "passive"))
      (node (ref "U4") (pin "4") (pinfunction "EN_4") (pintype "passive"))
    )
    (net (code "30") (name "Net-(U4-FB)") (class "Default")
      (node (ref "C40") (pin "1") (pinfunction "1_1") (pintype "passive"))
      (node (ref "R36") (pin "1") (pinfunction "1_1") (pintype "passive"))
      (node (ref "R40") (pin "2") (pinfunction "2_2") (pintype "passive"))
      (node (ref "U4") (pin "3") (pinfunction "FB_3") (pintype "passive"))
    )
    (net (code "31") (name "Net-(U4-SW)") (class "Default")
      (node (ref "C36") (pin "2") (pinfunction "2_2") (pintype "passive"))
      (node (ref "L3") (pin "1") (pinfunction "1_1") (pintype "passive"))
      (node (ref "U4") (pin "6") (pinfunction "SW_6") (pintype "passive"))
    )
    (net (code "32") (name "Net-(U5-BST)") (class "Default")
      (node (ref "C45") (pin "1") (pinfunction "1_1") (pintype "passive"))
      (node (ref "U5") (pin "1") (pinfunction "BST_1") (pintype "passive"))
    )
    (net (code "33") (name "Net-(U5-EN)") (class "Default")
      (node (ref "R37") (pin "2") (pinfunction "2_2") (pintype "passive"))
      (node (ref "R39") (pin "2") (pinfunction "2_2") (pintype "passive"))
      (node (ref "U5") (pin "4") (pinfunction "EN_4") (pintype "passive"))
    )
    (net (code "34") (name "Net-(U5-FB)") (class "Default")
      (node (ref "C340") (pin "1") (pinfunction "1_1") (pintype "passive"))
      (node (ref "R38") (pin "1") (pinfunction "1_1") (pintype "passive"))
      (node (ref "R42") (pin "2") (pinfunction "2_2") (pintype "passive"))
      (node (ref "U5") (pin "3") (pinfunction "FB_3") (pintype "passive"))
    )
    (net (code "35") (name "Net-(U5-SW)") (class "Default")
      (node (ref "C45") (pin "2") (pinfunction "2_2") (pintype "passive"))
      (node (ref "L4") (pin "1") (pinfunction "1_1") (pintype "passive"))
      (node (ref "U5") (pin "6") (pinfunction "SW_6") (pintype "passive"))
    )
    (net (code "36") (name "VDD_1V8_MAIN") (class "Default")
      (node (ref "C340") (pin "2") (pinfunction "2_2") (pintype "passive"))
      (node (ref "C48") (pin "1") (pinfunction "1_1") (pintype "passive"))
      (node (ref "C49") (pin "1") (pinfunction "1_1") (pintype "passive"))
      (node (ref "C50") (pin "1") (pinfunction "1_1") (pintype "passive"))
      (node (ref "L4") (pin "2") (pinfunction "2_2") (pintype "passive"))
      (node (ref "R38") (pin "2") (pinfunction "2_2") (pintype "passive"))
      (node (ref "TP8") (pin "1") (pinfunction "1_1") (pintype "passive"))
    )
    (net (code "37") (name "VDD_3V3_MAIN") (class "Default")
      (node (ref "C40") (pin "2") (pinfunction "2_2") (pintype "passive"))
      (node (ref "C41") (pin "1") (pinfunction "1_1") (pintype "passive"))
      (node (ref "C42") (pin "1") (pinfunction "1_1") (pintype "passive"))
      (node (ref "C43") (pin "1") (pinfunction "1_1") (pintype "passive"))
      (node (ref "L3") (pin "2") (pinfunction "2_2") (pintype "passive"))
      (node (ref "Q4") (pin "2") (pinfunction "SOURCE_2") (pintype "passive"))
      (node (ref "R36") (pin "2") (pinfunction "2_2") (pintype "passive"))
      (node (ref "R446") (pin "1") (pinfunction "1_1") (pintype "passive"))
      (node (ref "TP7") (pin "1") (pinfunction "1_1") (pintype "passive"))
    )
    (net (code "38") (name "VDD_3V3_SOM") (class "Default")
      (node (ref "C18") (pin "1") (pinfunction "1_1") (pintype "passive"))
      (node (ref "C19") (pin "1") (pinfunction "1_1") (pintype "passive"))
      (node (ref "CON4") (pin "4") (pinfunction "4_4") (pintype "passive"))
      (node (ref "CON4") (pin "5") (pinfunction "5_5") (pintype "passive"))
      (node (ref "F2") (pin "2") (pinfunction "2_2") (pintype "passive"))
      (node (ref "TP5") (pin "1") (pinfunction "1_1") (pintype "passive"))
    )
    (net (code "39") (name "VDD_3V3_SOM_OUT") (class "Default")
      (node (ref "R30") (pin "2") (pinfunction "2_2") (pintype "passive"))
      (node (ref "R35") (pin "2") (pinfunction "2_2") (pintype "passive"))
      (node (ref "R37") (pin "1") (pinfunction "1_1") (pintype "passive"))
      (node (ref "R43") (pin "2") (pinfunction "2_2") (pintype "passive"))
    )
    (net (code "40") (name "VDD_5V_MAIN") (class "Default")
      (node (ref "C16") (pin "1") (pinfunction "1_1") (pintype "passive"))
      (node (ref "C17") (pin "1") (pinfunction "1_1") (pintype "passive"))
      (node (ref "C22") (pin "2") (pinfunction "2_2") (pintype "passive"))
      (node (ref "C33") (pin "1") (pinfunction "1_1") (pintype "passive"))
      (node (ref "C34") (pin "1") (pinfunction "1_1") (pintype "passive"))
      (node (ref "C35") (pin "1") (pinfunction "1_1") (pintype "passive"))
      (node (ref "CON4") (pin "7") (pinfunction "7_7") (pintype "passive"))
      (node (ref "L2") (pin "2") (pinfunction "2_2") (pintype "passive"))
      (node (ref "R29") (pin "2") (pinfunction "2_2") (pintype "passive"))
      (node (ref "TP6") (pin "1") (pinfunction "1_1") (pintype "passive"))
    )
    (net (code "41") (name "VDD_12V_IN") (class "Default")
      (node (ref "CON2") (pin "1") (pinfunction "1_1") (pintype "passive"))
      (node (ref "CON3") (pin "1") (pinfunction "1_1") (pintype "passive"))
      (node (ref "F1") (pin "1") (pinfunction "1_1") (pintype "passive"))
      (node (ref "R19") (pin "2") (pinfunction "2_2") (pintype "passive"))
    )
    (net (code "42") (name "VDD_12V_MAIN") (class "Default")
      (node (ref "C11") (pin "1") (pinfunction "1_1") (pintype "passive"))
      (node (ref "C13") (pin "1") (pinfunction "1_1") (pintype "passive"))
      (node (ref "C23") (pin "1") (pinfunction "1_1") (pintype "passive"))
      (node (ref "C24") (pin "1") (pinfunction "1_1") (pintype "passive"))
      (node (ref "C26") (pin "1") (pinfunction "1_1") (pintype "passive"))
      (node (ref "C30") (pin "1") (pinfunction "1_1") (pintype "passive"))
      (node (ref "C31") (pin "1") (pinfunction "1_1") (pintype "passive"))
      (node (ref "C32") (pin "1") (pinfunction "1_1") (pintype "passive"))
      (node (ref "C37") (pin "1") (pinfunction "1_1") (pintype "passive"))
      (node (ref "C38") (pin "1") (pinfunction "1_1") (pintype "passive"))
      (node (ref "C39") (pin "1") (pinfunction "1_1") (pintype "passive"))
      (node (ref "C44") (pin "1") (pinfunction "1_1") (pintype "passive"))
      (node (ref "C46") (pin "1") (pinfunction "1_1") (pintype "passive"))
      (node (ref "C47") (pin "1") (pinfunction "1_1") (pintype "passive"))
      (node (ref "CON4") (pin "8") (pinfunction "8_8") (pintype "passive"))
      (node (ref "D1") (pin "2") (pinfunction "2_2") (pintype "passive"))
      (node (ref "Q3") (pin "2") (pinfunction "SOURCE_2") (pintype "passive"))
      (node (ref "R20") (pin "1") (pinfunction "1_1") (pintype "passive"))
      (node (ref "R27") (pin "1") (pinfunction "1_1") (pintype "passive"))
      (node (ref "U2") (pin "5") (pinfunction "VIN_5") (pintype "power_in"))
      (node (ref "U3") (pin "5") (pinfunction "VIN_5") (pintype "power_in"))
      (node (ref "U4") (pin "5") (pinfunction "VIN_5") (pintype "power_in"))
      (node (ref "U5") (pin "5") (pinfunction "VIN_5") (pintype "power_in"))
    )
    (net (code "43") (name "unconnected-(CON3-Pad3)") (class "Default")
      (node (ref "CON3") (pin "3") (pinfunction "3_3") (pintype "passive+no_connect"))
    )
    (net (code "44") (name "unconnected-(H5-Pad1)") (class "Default")
      (node (ref "H5") (pin "1") (pinfunction "1_1") (pintype "passive+no_connect"))
    )
    (net (code "45") (name "unconnected-(H6-Pad1)") (class "Default")
      (node (ref "H6") (pin "1") (pinfunction "1_1") (pintype "passive+no_connect"))
    )
    (net (code "46") (name "unconnected-(SW1-Pad3)") (class "Default")
      (node (ref "SW1") (pin "3") (pinfunction "3_3") (pintype "passive+no_connect"))
    )
    (net (code "47") (name "unconnected-(SW1-Pad4)") (class "Default")
      (node (ref "SW1") (pin "4") (pinfunction "4_4") (pintype "passive"))
    )
    (net (code "48") (name "unconnected-(SW1-Pad5)") (class "Default")
      (node (ref "SW1") (pin "5") (pinfunction "5_5") (pintype "passive"))
    )
  )
)
